# helmholtz-distribution-pcb.net
KiCad netlist of a schematic drawn in EAGLE
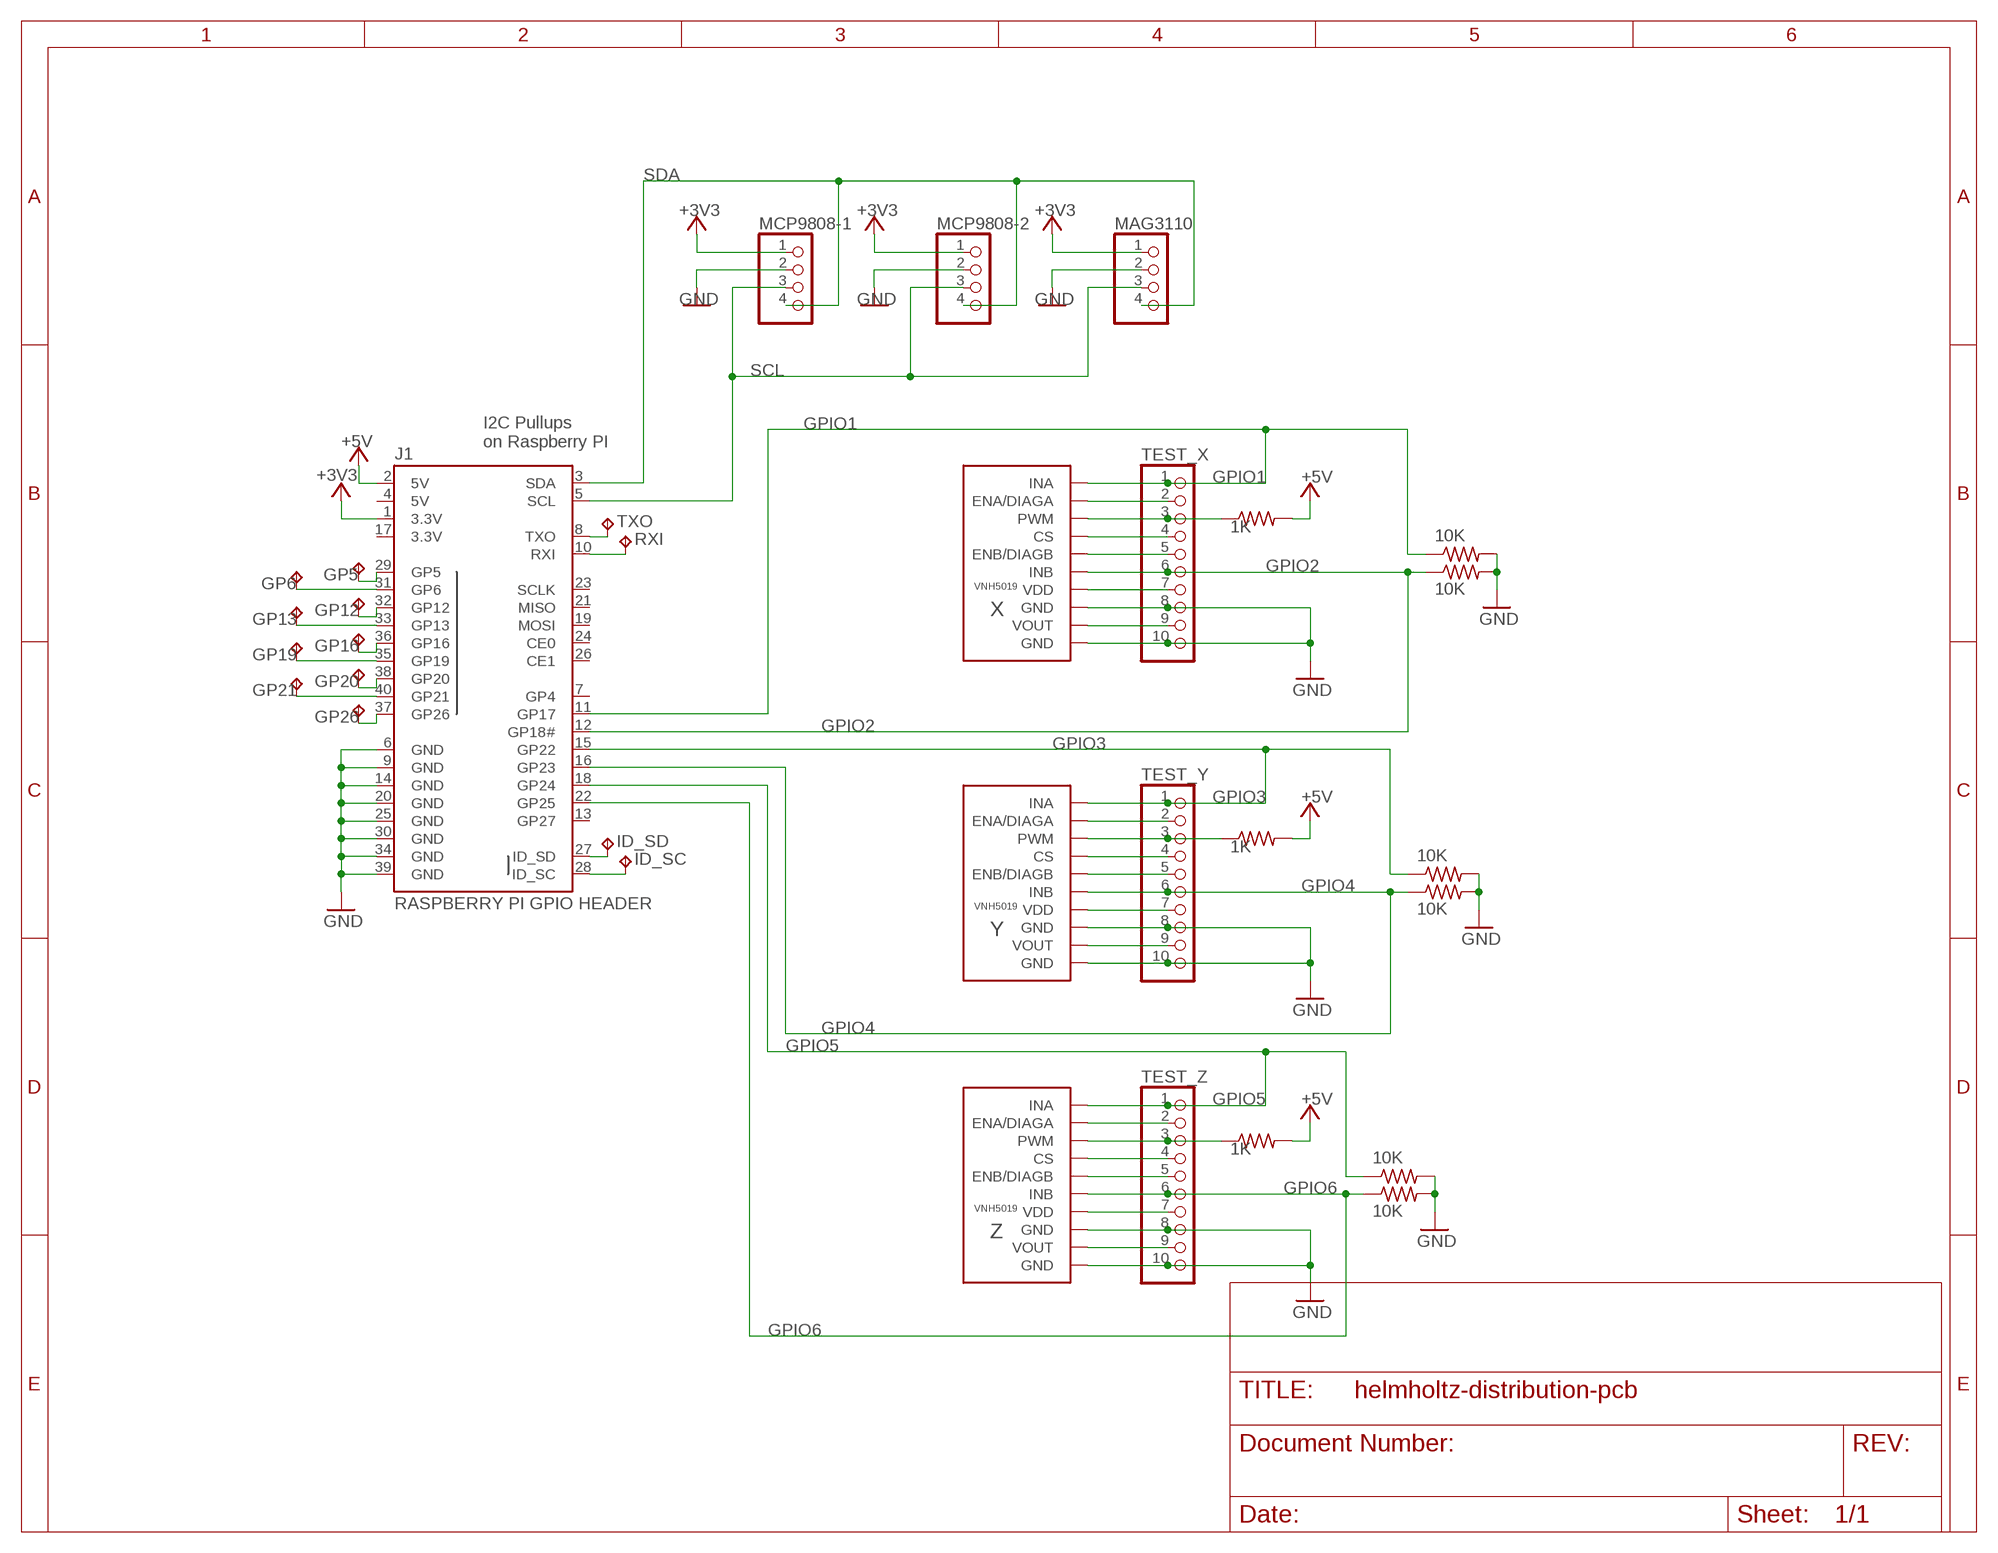
[diagram p0: schematic, sheet 1]

(export (version "E")
  (design (tool "Eeschema 10.0.6"))
  (components
    (comp (ref "GP5")
      (value "TPPAD1-13")
      (footprint "eagle-import:P1-13")
      (libsource (lib "eagle-import") (part "TPPAD1-13"))
    )
    (comp (ref "GP6")
      (value "TPPAD1-13")
      (footprint "eagle-import:P1-13")
      (libsource (lib "eagle-import") (part "TPPAD1-13"))
    )
    (comp (ref "GP12")
      (value "TPPAD1-13")
      (footprint "eagle-import:P1-13")
      (libsource (lib "eagle-import") (part "TPPAD1-13"))
    )
    (comp (ref "GP13")
      (value "TPPAD1-13")
      (footprint "eagle-import:P1-13")
      (libsource (lib "eagle-import") (part "TPPAD1-13"))
    )
    (comp (ref "GP16")
      (value "TPPAD1-13")
      (footprint "eagle-import:P1-13")
      (libsource (lib "eagle-import") (part "TPPAD1-13"))
    )
    (comp (ref "GP19")
      (value "TPPAD1-13")
      (footprint "eagle-import:P1-13")
      (libsource (lib "eagle-import") (part "TPPAD1-13"))
    )
    (comp (ref "GP20")
      (value "TPPAD1-13")
      (footprint "eagle-import:P1-13")
      (libsource (lib "eagle-import") (part "TPPAD1-13"))
    )
    (comp (ref "GP21")
      (value "TPPAD1-13")
      (footprint "eagle-import:P1-13")
      (libsource (lib "eagle-import") (part "TPPAD1-13"))
    )
    (comp (ref "GP26")
      (value "TPPAD1-13")
      (footprint "eagle-import:P1-13")
      (libsource (lib "eagle-import") (part "TPPAD1-13"))
    )
    (comp (ref "ID_SC")
      (value "TPPAD1-13")
      (footprint "eagle-import:P1-13")
      (libsource (lib "eagle-import") (part "TPPAD1-13"))
    )
    (comp (ref "ID_SD")
      (value "TPPAD1-13")
      (footprint "eagle-import:P1-13")
      (libsource (lib "eagle-import") (part "TPPAD1-13"))
    )
    (comp (ref "J1")
      (value "RASPBERRYPI-40-PIN-GPIO_PTH")
      (footprint "eagle-import:2X20_SHROUDED")
      (libsource (lib "eagle-import") (part "RASPBERRYPI-40-PIN-GPIO_PTH"))
    )
    (comp (ref "MAG3110")
      (value "PINHD-1X4")
      (footprint "eagle-import:1X04")
      (libsource (lib "eagle-import") (part "PINHD-1X4"))
    )
    (comp (ref "MCP9808-1")
      (value "PINHD-1X4")
      (footprint "eagle-import:1X04")
      (libsource (lib "eagle-import") (part "PINHD-1X4"))
    )
    (comp (ref "MCP9808-2")
      (value "PINHD-1X4")
      (footprint "eagle-import:1X04")
      (libsource (lib "eagle-import") (part "PINHD-1X4"))
    )
    (comp (ref "R2")
      (value "10K")
      (footprint "eagle-import:R0603")
      (libsource (lib "eagle-import") (part "R-US_R0603"))
    )
    (comp (ref "R3")
      (value "10K")
      (footprint "eagle-import:R0603")
      (libsource (lib "eagle-import") (part "R-US_R0603"))
    )
    (comp (ref "R7")
      (value "1K")
      (footprint "eagle-import:R0603")
      (libsource (lib "eagle-import") (part "R-US_R0603"))
    )
    (comp (ref "R9")
      (value "10K")
      (footprint "eagle-import:R0603")
      (libsource (lib "eagle-import") (part "R-US_R0603"))
    )
    (comp (ref "R10")
      (value "10K")
      (footprint "eagle-import:R0603")
      (libsource (lib "eagle-import") (part "R-US_R0603"))
    )
    (comp (ref "R13")
      (value "1K")
      (footprint "eagle-import:R0603")
      (libsource (lib "eagle-import") (part "R-US_R0603"))
    )
    (comp (ref "R16")
      (value "10K")
      (footprint "eagle-import:R0603")
      (libsource (lib "eagle-import") (part "R-US_R0603"))
    )
    (comp (ref "R17")
      (value "10K")
      (footprint "eagle-import:R0603")
      (libsource (lib "eagle-import") (part "R-US_R0603"))
    )
    (comp (ref "R20")
      (value "1K")
      (footprint "eagle-import:R0603")
      (libsource (lib "eagle-import") (part "R-US_R0603"))
    )
    (comp (ref "RXI")
      (value "TPPAD1-13")
      (footprint "eagle-import:P1-13")
      (libsource (lib "eagle-import") (part "TPPAD1-13"))
    )
    (comp (ref "TEST_X")
      (value "PINHD-1X10")
      (footprint "eagle-import:1X10")
      (libsource (lib "eagle-import") (part "PINHD-1X10"))
    )
    (comp (ref "TEST_Y")
      (value "PINHD-1X10")
      (footprint "eagle-import:1X10")
      (libsource (lib "eagle-import") (part "PINHD-1X10"))
    )
    (comp (ref "TEST_Z")
      (value "PINHD-1X10")
      (footprint "eagle-import:1X10")
      (libsource (lib "eagle-import") (part "PINHD-1X10"))
    )
    (comp (ref "TXO")
      (value "TPPAD1-13")
      (footprint "eagle-import:P1-13")
      (libsource (lib "eagle-import") (part "TPPAD1-13"))
    )
    (comp (ref "X")
      (value "VNH5019")
      (footprint "eagle-import:VNH5019")
      (libsource (lib "eagle-import") (part "VNH5019"))
    )
    (comp (ref "Y")
      (value "VNH5019")
      (footprint "eagle-import:VNH5019")
      (libsource (lib "eagle-import") (part "VNH5019"))
    )
    (comp (ref "Z")
      (value "VNH5019")
      (footprint "eagle-import:VNH5019")
      (libsource (lib "eagle-import") (part "VNH5019"))
    )
  )
  (nets
    (net (code "1") (name "+3V3") (class "Default")
      (node (ref "J1") (pin "1") (pinfunction "3.3V_1") (pintype "power_in"))
      (node (ref "MAG3110") (pin "1") (pinfunction "1_1") (pintype "passive"))
      (node (ref "MCP9808-1") (pin "1") (pinfunction "1_1") (pintype "passive"))
      (node (ref "MCP9808-2") (pin "1") (pinfunction "1_1") (pintype "passive"))
    )
    (net (code "2") (name "+5V") (class "Default")
      (node (ref "J1") (pin "2") (pinfunction "5V_2") (pintype "power_in"))
      (node (ref "R13") (pin "2") (pinfunction "2_2") (pintype "passive"))
      (node (ref "R20") (pin "2") (pinfunction "2_2") (pintype "passive"))
      (node (ref "R7") (pin "2") (pinfunction "2_2") (pintype "passive"))
    )
    (net (code "3") (name "/3.3V") (class "Default")
      (node (ref "J1") (pin "17") (pinfunction "3.3V_17") (pintype "power_in"))
    )
    (net (code "4") (name "/5V") (class "Default")
      (node (ref "J1") (pin "4") (pinfunction "5V_4") (pintype "power_in"))
    )
    (net (code "5") (name "/GPIO1") (class "Default")
      (node (ref "J1") (pin "11") (pinfunction "GP17_11") (pintype "bidirectional"))
      (node (ref "R17") (pin "1") (pinfunction "1_1") (pintype "passive"))
      (node (ref "TEST_X") (pin "1") (pinfunction "1_1") (pintype "passive"))
      (node (ref "X") (pin "INA") (pinfunction "INA_INA") (pintype "input"))
    )
    (net (code "6") (name "/GPIO2") (class "Default")
      (node (ref "J1") (pin "12") (pinfunction "GP18#_12") (pintype "bidirectional"))
      (node (ref "R16") (pin "1") (pinfunction "1_1") (pintype "passive"))
      (node (ref "TEST_X") (pin "6") (pinfunction "6_6") (pintype "passive"))
      (node (ref "X") (pin "INB") (pinfunction "INB_INB") (pintype "input"))
    )
    (net (code "7") (name "/GPIO3") (class "Default")
      (node (ref "J1") (pin "15") (pinfunction "GP22_15") (pintype "bidirectional"))
      (node (ref "R10") (pin "1") (pinfunction "1_1") (pintype "passive"))
      (node (ref "TEST_Y") (pin "1") (pinfunction "1_1") (pintype "passive"))
      (node (ref "Y") (pin "INA") (pinfunction "INA_INA") (pintype "input"))
    )
    (net (code "8") (name "/GPIO4") (class "Default")
      (node (ref "J1") (pin "16") (pinfunction "GP23_16") (pintype "bidirectional"))
      (node (ref "R9") (pin "1") (pinfunction "1_1") (pintype "passive"))
      (node (ref "TEST_Y") (pin "6") (pinfunction "6_6") (pintype "passive"))
      (node (ref "Y") (pin "INB") (pinfunction "INB_INB") (pintype "input"))
    )
    (net (code "9") (name "/GPIO5") (class "Default")
      (node (ref "J1") (pin "18") (pinfunction "GP24_18") (pintype "bidirectional"))
      (node (ref "R3") (pin "1") (pinfunction "1_1") (pintype "passive"))
      (node (ref "TEST_Z") (pin "1") (pinfunction "1_1") (pintype "passive"))
      (node (ref "Z") (pin "INA") (pinfunction "INA_INA") (pintype "input"))
    )
    (net (code "10") (name "/GPIO6") (class "Default")
      (node (ref "J1") (pin "22") (pinfunction "GP25_22") (pintype "bidirectional"))
      (node (ref "R2") (pin "1") (pinfunction "1_1") (pintype "passive"))
      (node (ref "TEST_Z") (pin "6") (pinfunction "6_6") (pintype "passive"))
      (node (ref "Z") (pin "INB") (pinfunction "INB_INB") (pintype "input"))
    )
    (net (code "11") (name "/SCL") (class "Default")
      (node (ref "J1") (pin "5") (pinfunction "SCL_5") (pintype "bidirectional"))
      (node (ref "MAG3110") (pin "3") (pinfunction "3_3") (pintype "passive"))
      (node (ref "MCP9808-1") (pin "3") (pinfunction "3_3") (pintype "passive"))
      (node (ref "MCP9808-2") (pin "3") (pinfunction "3_3") (pintype "passive"))
    )
    (net (code "12") (name "/SDA") (class "Default")
      (node (ref "J1") (pin "3") (pinfunction "SDA_3") (pintype "bidirectional"))
      (node (ref "MAG3110") (pin "4") (pinfunction "4_4") (pintype "passive"))
      (node (ref "MCP9808-1") (pin "4") (pinfunction "4_4") (pintype "passive"))
      (node (ref "MCP9808-2") (pin "4") (pinfunction "4_4") (pintype "passive"))
    )
    (net (code "13") (name "GND") (class "Default")
      (node (ref "J1") (pin "14") (pinfunction "GND_14") (pintype "power_in"))
      (node (ref "J1") (pin "20") (pinfunction "GND_20") (pintype "power_in"))
      (node (ref "J1") (pin "25") (pinfunction "GND_25") (pintype "power_in"))
      (node (ref "J1") (pin "30") (pinfunction "GND_30") (pintype "power_in"))
      (node (ref "J1") (pin "34") (pinfunction "GND_34") (pintype "power_in"))
      (node (ref "J1") (pin "39") (pinfunction "GND_39") (pintype "power_in"))
      (node (ref "J1") (pin "6") (pinfunction "GND_6") (pintype "power_in"))
      (node (ref "J1") (pin "9") (pinfunction "GND_9") (pintype "power_in"))
      (node (ref "MAG3110") (pin "2") (pinfunction "2_2") (pintype "passive"))
      (node (ref "MCP9808-1") (pin "2") (pinfunction "2_2") (pintype "passive"))
      (node (ref "MCP9808-2") (pin "2") (pinfunction "2_2") (pintype "passive"))
      (node (ref "R10") (pin "2") (pinfunction "2_2") (pintype "passive"))
      (node (ref "R16") (pin "2") (pinfunction "2_2") (pintype "passive"))
      (node (ref "R17") (pin "2") (pinfunction "2_2") (pintype "passive"))
      (node (ref "R2") (pin "2") (pinfunction "2_2") (pintype "passive"))
      (node (ref "R3") (pin "2") (pinfunction "2_2") (pintype "passive"))
      (node (ref "R9") (pin "2") (pinfunction "2_2") (pintype "passive"))
      (node (ref "TEST_X") (pin "10") (pinfunction "10_10") (pintype "passive"))
      (node (ref "TEST_X") (pin "8") (pinfunction "8_8") (pintype "passive"))
      (node (ref "TEST_Y") (pin "10") (pinfunction "10_10") (pintype "passive"))
      (node (ref "TEST_Y") (pin "8") (pinfunction "8_8") (pintype "passive"))
      (node (ref "TEST_Z") (pin "10") (pinfunction "10_10") (pintype "passive"))
      (node (ref "TEST_Z") (pin "8") (pinfunction "8_8") (pintype "passive"))
      (node (ref "X") (pin "GND@1") (pinfunction "GND_GND@1") (pintype "power_in"))
      (node (ref "X") (pin "GND@2") (pinfunction "GND_GND@2") (pintype "power_in"))
      (node (ref "Y") (pin "GND@1") (pinfunction "GND_GND@1") (pintype "power_in"))
      (node (ref "Y") (pin "GND@2") (pinfunction "GND_GND@2") (pintype "power_in"))
      (node (ref "Z") (pin "GND@1") (pinfunction "GND_GND@1") (pintype "power_in"))
      (node (ref "Z") (pin "GND@2") (pinfunction "GND_GND@2") (pintype "power_in"))
    )
    (net (code "14") (name "Net-(J1-GP5)") (class "Default")
      (node (ref "GP5") (pin "TP") (pinfunction "TP_TP") (pintype "input"))
      (node (ref "J1") (pin "29") (pinfunction "GP5_29") (pintype "bidirectional"))
    )
    (net (code "15") (name "Net-(J1-GP6)") (class "Default")
      (node (ref "GP6") (pin "TP") (pinfunction "TP_TP") (pintype "input"))
      (node (ref "J1") (pin "31") (pinfunction "GP6_31") (pintype "bidirectional"))
    )
    (net (code "16") (name "Net-(J1-GP12)") (class "Default")
      (node (ref "GP12") (pin "TP") (pinfunction "TP_TP") (pintype "input"))
      (node (ref "J1") (pin "32") (pinfunction "GP12_32") (pintype "bidirectional"))
    )
    (net (code "17") (name "Net-(J1-GP13)") (class "Default")
      (node (ref "GP13") (pin "TP") (pinfunction "TP_TP") (pintype "input"))
      (node (ref "J1") (pin "33") (pinfunction "GP13_33") (pintype "bidirectional"))
    )
    (net (code "18") (name "Net-(J1-GP16)") (class "Default")
      (node (ref "GP16") (pin "TP") (pinfunction "TP_TP") (pintype "input"))
      (node (ref "J1") (pin "36") (pinfunction "GP16_36") (pintype "bidirectional"))
    )
    (net (code "19") (name "Net-(J1-GP19)") (class "Default")
      (node (ref "GP19") (pin "TP") (pinfunction "TP_TP") (pintype "input"))
      (node (ref "J1") (pin "35") (pinfunction "GP19_35") (pintype "bidirectional"))
    )
    (net (code "20") (name "Net-(J1-GP20)") (class "Default")
      (node (ref "GP20") (pin "TP") (pinfunction "TP_TP") (pintype "input"))
      (node (ref "J1") (pin "38") (pinfunction "GP20_38") (pintype "bidirectional"))
    )
    (net (code "21") (name "Net-(J1-GP21)") (class "Default")
      (node (ref "GP21") (pin "TP") (pinfunction "TP_TP") (pintype "input"))
      (node (ref "J1") (pin "40") (pinfunction "GP21_40") (pintype "bidirectional"))
    )
    (net (code "22") (name "Net-(J1-GP26)") (class "Default")
      (node (ref "GP26") (pin "TP") (pinfunction "TP_TP") (pintype "input"))
      (node (ref "J1") (pin "37") (pinfunction "GP26_37") (pintype "bidirectional"))
    )
    (net (code "23") (name "Net-(J1-ID_SC)") (class "Default")
      (node (ref "ID_SC") (pin "TP") (pinfunction "TP_TP") (pintype "input"))
      (node (ref "J1") (pin "28") (pinfunction "ID_SC_28") (pintype "bidirectional"))
    )
    (net (code "24") (name "Net-(J1-ID_SD)") (class "Default")
      (node (ref "ID_SD") (pin "TP") (pinfunction "TP_TP") (pintype "input"))
      (node (ref "J1") (pin "27") (pinfunction "ID_SD_27") (pintype "bidirectional"))
    )
    (net (code "25") (name "Net-(J1-RXI)") (class "Default")
      (node (ref "J1") (pin "10") (pinfunction "RXI_10") (pintype "input"))
      (node (ref "RXI") (pin "TP") (pinfunction "TP_TP") (pintype "input"))
    )
    (net (code "26") (name "Net-(J1-TXO)") (class "Default")
      (node (ref "J1") (pin "8") (pinfunction "TXO_8") (pintype "output"))
      (node (ref "TXO") (pin "TP") (pinfunction "TP_TP") (pintype "input"))
    )
    (net (code "27") (name "Net-(R7-Pad1)") (class "Default")
      (node (ref "R7") (pin "1") (pinfunction "1_1") (pintype "passive"))
      (node (ref "TEST_Z") (pin "3") (pinfunction "3_3") (pintype "passive"))
      (node (ref "Z") (pin "PWM") (pinfunction "PWM_PWM") (pintype "input"))
    )
    (net (code "28") (name "Net-(R13-Pad1)") (class "Default")
      (node (ref "R13") (pin "1") (pinfunction "1_1") (pintype "passive"))
      (node (ref "TEST_Y") (pin "3") (pinfunction "3_3") (pintype "passive"))
      (node (ref "Y") (pin "PWM") (pinfunction "PWM_PWM") (pintype "input"))
    )
    (net (code "29") (name "Net-(R20-Pad1)") (class "Default")
      (node (ref "R20") (pin "1") (pinfunction "1_1") (pintype "passive"))
      (node (ref "TEST_X") (pin "3") (pinfunction "3_3") (pintype "passive"))
      (node (ref "X") (pin "PWM") (pinfunction "PWM_PWM") (pintype "input"))
    )
    (net (code "30") (name "Net-(TEST_X-Pad2)") (class "Default")
      (node (ref "TEST_X") (pin "2") (pinfunction "2_2") (pintype "passive"))
      (node (ref "X") (pin "ENA/DIAGA") (pinfunction "ENA/DIAGA_ENA/DIAGA") (pintype "bidirectional"))
    )
    (net (code "31") (name "Net-(TEST_X-Pad4)") (class "Default")
      (node (ref "TEST_X") (pin "4") (pinfunction "4_4") (pintype "passive"))
      (node (ref "X") (pin "CS") (pinfunction "CS_CS") (pintype "output"))
    )
    (net (code "32") (name "Net-(TEST_X-Pad7)") (class "Default")
      (node (ref "TEST_X") (pin "7") (pinfunction "7_7") (pintype "passive"))
      (node (ref "X") (pin "VDD") (pinfunction "VDD_VDD") (pintype "power_in"))
    )
    (net (code "33") (name "Net-(TEST_X-Pad9)") (class "Default")
      (node (ref "TEST_X") (pin "9") (pinfunction "9_9") (pintype "passive"))
      (node (ref "X") (pin "VOUT") (pinfunction "VOUT_VOUT") (pintype "power_in"))
    )
    (net (code "34") (name "Net-(TEST_Y-Pad2)") (class "Default")
      (node (ref "TEST_Y") (pin "2") (pinfunction "2_2") (pintype "passive"))
      (node (ref "Y") (pin "ENA/DIAGA") (pinfunction "ENA/DIAGA_ENA/DIAGA") (pintype "bidirectional"))
    )
    (net (code "35") (name "Net-(TEST_Y-Pad4)") (class "Default")
      (node (ref "TEST_Y") (pin "4") (pinfunction "4_4") (pintype "passive"))
      (node (ref "Y") (pin "CS") (pinfunction "CS_CS") (pintype "output"))
    )
    (net (code "36") (name "Net-(TEST_Y-Pad7)") (class "Default")
      (node (ref "TEST_Y") (pin "7") (pinfunction "7_7") (pintype "passive"))
      (node (ref "Y") (pin "VDD") (pinfunction "VDD_VDD") (pintype "power_in"))
    )
    (net (code "37") (name "Net-(TEST_Y-Pad9)") (class "Default")
      (node (ref "TEST_Y") (pin "9") (pinfunction "9_9") (pintype "passive"))
      (node (ref "Y") (pin "VOUT") (pinfunction "VOUT_VOUT") (pintype "power_in"))
    )
    (net (code "38") (name "Net-(TEST_Z-Pad2)") (class "Default")
      (node (ref "TEST_Z") (pin "2") (pinfunction "2_2") (pintype "passive"))
      (node (ref "Z") (pin "ENA/DIAGA") (pinfunction "ENA/DIAGA_ENA/DIAGA") (pintype "bidirectional"))
    )
    (net (code "39") (name "Net-(TEST_Z-Pad4)") (class "Default")
      (node (ref "TEST_Z") (pin "4") (pinfunction "4_4") (pintype "passive"))
      (node (ref "Z") (pin "CS") (pinfunction "CS_CS") (pintype "output"))
    )
    (net (code "40") (name "Net-(TEST_Z-Pad7)") (class "Default")
      (node (ref "TEST_Z") (pin "7") (pinfunction "7_7") (pintype "passive"))
      (node (ref "Z") (pin "VDD") (pinfunction "VDD_VDD") (pintype "power_in"))
    )
    (net (code "41") (name "Net-(TEST_Z-Pad9)") (class "Default")
      (node (ref "TEST_Z") (pin "9") (pinfunction "9_9") (pintype "passive"))
      (node (ref "Z") (pin "VOUT") (pinfunction "VOUT_VOUT") (pintype "power_in"))
    )
    (net (code "42") (name "Net-(X-ENB{slash}DIAGB)") (class "Default")
      (node (ref "TEST_X") (pin "5") (pinfunction "5_5") (pintype "passive"))
      (node (ref "X") (pin "EBN/DIAGB") (pinfunction "ENB/DIAGB_EBN/DIAGB") (pintype "bidirectional"))
    )
    (net (code "43") (name "Net-(Y-ENB{slash}DIAGB)") (class "Default")
      (node (ref "TEST_Y") (pin "5") (pinfunction "5_5") (pintype "passive"))
      (node (ref "Y") (pin "EBN/DIAGB") (pinfunction "ENB/DIAGB_EBN/DIAGB") (pintype "bidirectional"))
    )
    (net (code "44") (name "Net-(Z-ENB{slash}DIAGB)") (class "Default")
      (node (ref "TEST_Z") (pin "5") (pinfunction "5_5") (pintype "passive"))
      (node (ref "Z") (pin "EBN/DIAGB") (pinfunction "ENB/DIAGB_EBN/DIAGB") (pintype "bidirectional"))
    )
    (net (code "45") (name "unconnected-(J1-CE0-Pad24)") (class "Default")
      (node (ref "J1") (pin "24") (pinfunction "CE0_24") (pintype "output"))
    )
    (net (code "46") (name "unconnected-(J1-CE1-Pad26)") (class "Default")
      (node (ref "J1") (pin "26") (pinfunction "CE1_26") (pintype "output"))
    )
    (net (code "47") (name "unconnected-(J1-GP4-Pad7)") (class "Default")
      (node (ref "J1") (pin "7") (pinfunction "GP4_7") (pintype "bidirectional"))
    )
    (net (code "48") (name "unconnected-(J1-GP27-Pad13)") (class "Default")
      (node (ref "J1") (pin "13") (pinfunction "GP27_13") (pintype "bidirectional"))
    )
    (net (code "49") (name "unconnected-(J1-MISO-Pad21)") (class "Default")
      (node (ref "J1") (pin "21") (pinfunction "MISO_21") (pintype "input"))
    )
    (net (code "50") (name "unconnected-(J1-MOSI-Pad19)") (class "Default")
      (node (ref "J1") (pin "19") (pinfunction "MOSI_19") (pintype "output"))
    )
    (net (code "51") (name "unconnected-(J1-SCLK-Pad23)") (class "Default")
      (node (ref "J1") (pin "23") (pinfunction "SCLK_23") (pintype "output"))
    )
  )
)
